# Controller-II.net
KiCad netlist of a schematic drawn in EAGLE
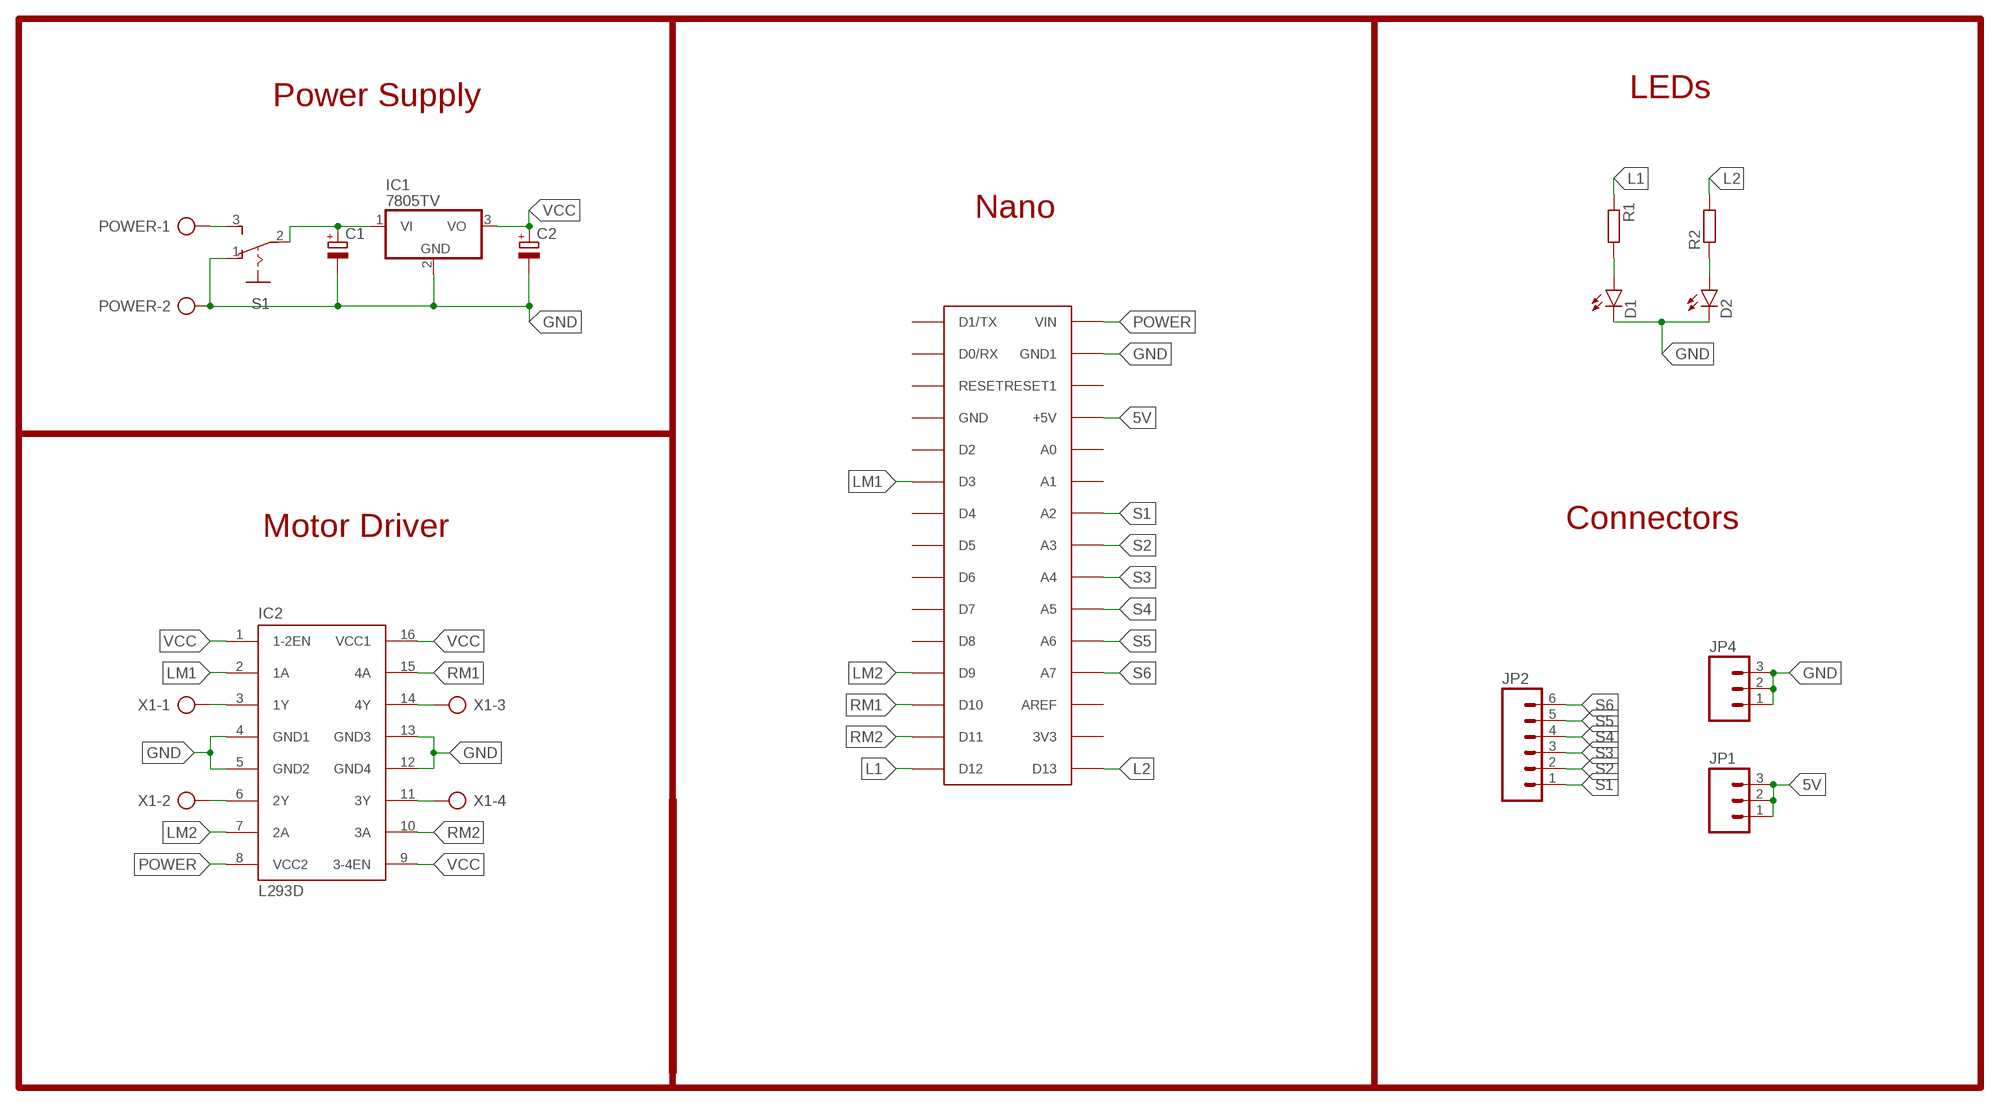
[diagram p0: schematic, sheet 1]

(export (version "E")
  (design (tool "Eeschema 10.0.6"))
  (components
    (comp (ref "C1")
      (value "CPOL-EUE5-10.5")
      (footprint "eagle-import:E5-10,5")
      (libsource (lib "eagle-import") (part "CPOL-EUE5-10.5"))
    )
    (comp (ref "C2")
      (value "CPOL-EUE5-10.5")
      (footprint "eagle-import:E5-10,5")
      (libsource (lib "eagle-import") (part "CPOL-EUE5-10.5"))
    )
    (comp (ref "D1")
      (value "LED5MM")
      (footprint "eagle-import:LED5MM")
      (libsource (lib "eagle-import") (part "LED5MM"))
    )
    (comp (ref "D2")
      (value "LED5MM")
      (footprint "eagle-import:LED5MM")
      (libsource (lib "eagle-import") (part "LED5MM"))
    )
    (comp (ref "IC1")
      (value "7805TV")
      (footprint "eagle-import:TO220V")
      (libsource (lib "eagle-import") (part "78TV05"))
    )
    (comp (ref "IC2")
      (value "L293D")
      (footprint "eagle-import:DIL16")
      (libsource (lib "eagle-import") (part "L293D"))
    )
    (comp (ref "JP1")
      (value "M031X03_NO_SILK")
      (footprint "eagle-import:1X03_NO_SILK")
      (libsource (lib "eagle-import") (part "M031X03_NO_SILK"))
    )
    (comp (ref "JP2")
      (value "M06NO_SILK_FEMALE_PTH")
      (footprint "eagle-import:1X06_NO_SILK")
      (libsource (lib "eagle-import") (part "M06NO_SILK_FEMALE_PTH"))
    )
    (comp (ref "JP4")
      (value "M031X03_NO_SILK")
      (footprint "eagle-import:1X03_NO_SILK")
      (libsource (lib "eagle-import") (part "M031X03_NO_SILK"))
    )
    (comp (ref "POWER")
      (value "AK300/2")
      (footprint "eagle-import:AK300_2")
      (libsource (lib "eagle-import") (part "AK300/2"))
    )
    (comp (ref "R1")
      (value "R-EU_0204/5")
      (footprint "eagle-import:0204_5")
      (libsource (lib "eagle-import") (part "R-EU_0204/5"))
    )
    (comp (ref "R2")
      (value "R-EU_0204/5")
      (footprint "eagle-import:0204_5")
      (libsource (lib "eagle-import") (part "R-EU_0204/5"))
    )
    (comp (ref "S1")
      (value "255SB")
      (footprint "eagle-import:255SB")
      (libsource (lib "eagle-import") (part "255SB"))
    )
    (comp (ref "U1")
      (value "ARDUINONANO")
      (footprint "eagle-import:PDIP-32")
      (libsource (lib "eagle-import") (part "ARDUINONANO"))
    )
    (comp (ref "X1")
      (value "AK300/4")
      (footprint "eagle-import:AK300_4")
      (libsource (lib "eagle-import") (part "AK300/4"))
    )
  )
  (nets
    (net (code "1") (name "5V") (class "Default")
      (node (ref "JP1") (pin "1") (pinfunction "1_1") (pintype "passive"))
      (node (ref "JP1") (pin "2") (pinfunction "2_2") (pintype "passive"))
      (node (ref "JP1") (pin "3") (pinfunction "3_3") (pintype "passive"))
      (node (ref "U1") (pin "+5V") (pinfunction "+5V_+5V") (pintype "bidirectional"))
    )
    (net (code "2") (name "GND") (class "Default")
      (node (ref "C1") (pin "-") (pinfunction "-_-") (pintype "passive"))
      (node (ref "C2") (pin "-") (pinfunction "-_-") (pintype "passive"))
      (node (ref "D1") (pin "K") (pinfunction "C_K") (pintype "passive"))
      (node (ref "D2") (pin "K") (pinfunction "C_K") (pintype "passive"))
      (node (ref "IC1") (pin "2") (pinfunction "GND_2") (pintype "passive"))
      (node (ref "IC2") (pin "12") (pinfunction "GND4_12") (pintype "power_in"))
      (node (ref "IC2") (pin "13") (pinfunction "GND3_13") (pintype "power_in"))
      (node (ref "IC2") (pin "4") (pinfunction "GND1_4") (pintype "power_in"))
      (node (ref "IC2") (pin "5") (pinfunction "GND2_5") (pintype "power_in"))
      (node (ref "JP4") (pin "1") (pinfunction "1_1") (pintype "passive"))
      (node (ref "JP4") (pin "2") (pinfunction "2_2") (pintype "passive"))
      (node (ref "JP4") (pin "3") (pinfunction "3_3") (pintype "passive"))
      (node (ref "POWER") (pin "2") (pinfunction "KL_2") (pintype "passive"))
      (node (ref "S1") (pin "1") (pinfunction "O_1") (pintype "passive"))
      (node (ref "U1") (pin "GND1") (pinfunction "GND1_GND1") (pintype "bidirectional"))
    )
    (net (code "3") (name "L1") (class "Default")
      (node (ref "R1") (pin "1") (pinfunction "1_1") (pintype "passive"))
      (node (ref "U1") (pin "D12") (pinfunction "D12_D12") (pintype "bidirectional"))
    )
    (net (code "4") (name "L2") (class "Default")
      (node (ref "R2") (pin "2") (pinfunction "2_2") (pintype "passive"))
      (node (ref "U1") (pin "D13") (pinfunction "D13_D13") (pintype "bidirectional"))
    )
    (net (code "5") (name "LM1") (class "Default")
      (node (ref "IC2") (pin "2") (pinfunction "1A_2") (pintype "input"))
      (node (ref "U1") (pin "D3") (pinfunction "D3_D3") (pintype "bidirectional"))
    )
    (net (code "6") (name "LM2") (class "Default")
      (node (ref "IC2") (pin "7") (pinfunction "2A_7") (pintype "input"))
      (node (ref "U1") (pin "D9") (pinfunction "D9_D9") (pintype "bidirectional"))
    )
    (net (code "7") (name "Net-(D1-PadA)") (class "Default")
      (node (ref "D1") (pin "A") (pinfunction "A_A") (pintype "passive"))
      (node (ref "R1") (pin "2") (pinfunction "2_2") (pintype "passive"))
    )
    (net (code "8") (name "Net-(D2-PadA)") (class "Default")
      (node (ref "D2") (pin "A") (pinfunction "A_A") (pintype "passive"))
      (node (ref "R2") (pin "1") (pinfunction "1_1") (pintype "passive"))
    )
    (net (code "9") (name "Net-(IC1-VI)") (class "Default")
      (node (ref "C1") (pin "+") (pinfunction "+_+") (pintype "passive"))
      (node (ref "IC1") (pin "1") (pinfunction "VI_1") (pintype "input"))
      (node (ref "S1") (pin "2") (pinfunction "P_2") (pintype "passive"))
    )
    (net (code "10") (name "Net-(IC2-1Y)") (class "Default")
      (node (ref "IC2") (pin "3") (pinfunction "1Y_3") (pintype "output"))
      (node (ref "X1") (pin "1") (pinfunction "KL_1") (pintype "passive"))
    )
    (net (code "11") (name "Net-(IC2-2Y)") (class "Default")
      (node (ref "IC2") (pin "6") (pinfunction "2Y_6") (pintype "output"))
      (node (ref "X1") (pin "2") (pinfunction "KL_2") (pintype "passive"))
    )
    (net (code "12") (name "Net-(IC2-3Y)") (class "Default")
      (node (ref "IC2") (pin "11") (pinfunction "3Y_11") (pintype "output"))
      (node (ref "X1") (pin "4") (pinfunction "KL_4") (pintype "passive"))
    )
    (net (code "13") (name "Net-(IC2-4Y)") (class "Default")
      (node (ref "IC2") (pin "14") (pinfunction "4Y_14") (pintype "output"))
      (node (ref "X1") (pin "3") (pinfunction "KL_3") (pintype "passive"))
    )
    (net (code "14") (name "POWER") (class "Default")
      (node (ref "IC2") (pin "8") (pinfunction "VCC2_8") (pintype "power_in"))
      (node (ref "POWER") (pin "1") (pinfunction "KL_1") (pintype "passive"))
      (node (ref "S1") (pin "3") (pinfunction "S_3") (pintype "passive"))
      (node (ref "U1") (pin "VIN") (pinfunction "VIN_VIN") (pintype "bidirectional"))
    )
    (net (code "15") (name "RM1") (class "Default")
      (node (ref "IC2") (pin "15") (pinfunction "4A_15") (pintype "input"))
      (node (ref "U1") (pin "D10") (pinfunction "D10_D10") (pintype "bidirectional"))
    )
    (net (code "16") (name "RM2") (class "Default")
      (node (ref "IC2") (pin "10") (pinfunction "3A_10") (pintype "input"))
      (node (ref "U1") (pin "D11") (pinfunction "D11_D11") (pintype "bidirectional"))
    )
    (net (code "17") (name "S1") (class "Default")
      (node (ref "JP2") (pin "1") (pinfunction "1_1") (pintype "passive"))
      (node (ref "U1") (pin "A2") (pinfunction "A2_A2") (pintype "bidirectional"))
    )
    (net (code "18") (name "S2") (class "Default")
      (node (ref "JP2") (pin "2") (pinfunction "2_2") (pintype "passive"))
      (node (ref "U1") (pin "A3") (pinfunction "A3_A3") (pintype "bidirectional"))
    )
    (net (code "19") (name "S3") (class "Default")
      (node (ref "JP2") (pin "3") (pinfunction "3_3") (pintype "passive"))
      (node (ref "U1") (pin "A4") (pinfunction "A4_A4") (pintype "bidirectional"))
    )
    (net (code "20") (name "S4") (class "Default")
      (node (ref "JP2") (pin "4") (pinfunction "4_4") (pintype "passive"))
      (node (ref "U1") (pin "A5") (pinfunction "A5_A5") (pintype "bidirectional"))
    )
    (net (code "21") (name "S5") (class "Default")
      (node (ref "JP2") (pin "5") (pinfunction "5_5") (pintype "passive"))
      (node (ref "U1") (pin "A6") (pinfunction "A6_A6") (pintype "bidirectional"))
    )
    (net (code "22") (name "S6") (class "Default")
      (node (ref "JP2") (pin "6") (pinfunction "6_6") (pintype "passive"))
      (node (ref "U1") (pin "A7") (pinfunction "A7_A7") (pintype "bidirectional"))
    )
    (net (code "23") (name "VCC") (class "Default")
      (node (ref "C2") (pin "+") (pinfunction "+_+") (pintype "passive"))
      (node (ref "IC1") (pin "3") (pinfunction "VO_3") (pintype "passive"))
      (node (ref "IC2") (pin "1") (pinfunction "1-2EN_1") (pintype "input"))
      (node (ref "IC2") (pin "16") (pinfunction "VCC1_16") (pintype "power_in"))
      (node (ref "IC2") (pin "9") (pinfunction "3-4EN_9") (pintype "input"))
    )
    (net (code "24") (name "unconnected-(U1-Pad3V3)") (class "Default")
      (node (ref "U1") (pin "3V3") (pinfunction "3V3_3V3") (pintype "bidirectional"))
    )
    (net (code "25") (name "unconnected-(U1-PadA0)") (class "Default")
      (node (ref "U1") (pin "A0") (pinfunction "A0_A0") (pintype "bidirectional"))
    )
    (net (code "26") (name "unconnected-(U1-PadA1)") (class "Default")
      (node (ref "U1") (pin "A1") (pinfunction "A1_A1") (pintype "bidirectional"))
    )
    (net (code "27") (name "unconnected-(U1-PadAREF)") (class "Default")
      (node (ref "U1") (pin "AREF") (pinfunction "AREF_AREF") (pintype "bidirectional"))
    )
    (net (code "28") (name "unconnected-(U1-PadD0{slash}RX)") (class "Default")
      (node (ref "U1") (pin "D0/RX") (pinfunction "D0/RX_D0/RX") (pintype "bidirectional"))
    )
    (net (code "29") (name "unconnected-(U1-PadD1{slash}TX)") (class "Default")
      (node (ref "U1") (pin "D1/TX") (pinfunction "D1/TX_D1/TX") (pintype "bidirectional"))
    )
    (net (code "30") (name "unconnected-(U1-PadD2)") (class "Default")
      (node (ref "U1") (pin "D2") (pinfunction "D2_D2") (pintype "bidirectional"))
    )
    (net (code "31") (name "unconnected-(U1-PadD4)") (class "Default")
      (node (ref "U1") (pin "D4") (pinfunction "D4_D4") (pintype "bidirectional"))
    )
    (net (code "32") (name "unconnected-(U1-PadD5)") (class "Default")
      (node (ref "U1") (pin "D5") (pinfunction "D5_D5") (pintype "bidirectional"))
    )
    (net (code "33") (name "unconnected-(U1-PadD6)") (class "Default")
      (node (ref "U1") (pin "D6") (pinfunction "D6_D6") (pintype "bidirectional"))
    )
    (net (code "34") (name "unconnected-(U1-PadD7)") (class "Default")
      (node (ref "U1") (pin "D7") (pinfunction "D7_D7") (pintype "bidirectional"))
    )
    (net (code "35") (name "unconnected-(U1-PadD8)") (class "Default")
      (node (ref "U1") (pin "D8") (pinfunction "D8_D8") (pintype "bidirectional"))
    )
    (net (code "36") (name "unconnected-(U1-PadGND)") (class "Default")
      (node (ref "U1") (pin "GND") (pinfunction "GND_GND") (pintype "bidirectional"))
    )
    (net (code "37") (name "unconnected-(U1-PadRESET)") (class "Default")
      (node (ref "U1") (pin "RESET") (pinfunction "RESET_RESET") (pintype "bidirectional"))
    )
    (net (code "38") (name "unconnected-(U1-PadRESET1)") (class "Default")
      (node (ref "U1") (pin "RESET1") (pinfunction "RESET1_RESET1") (pintype "bidirectional"))
    )
  )
)
